# SmartStepp_v2.net
KiCad netlist of a schematic drawn in EAGLE
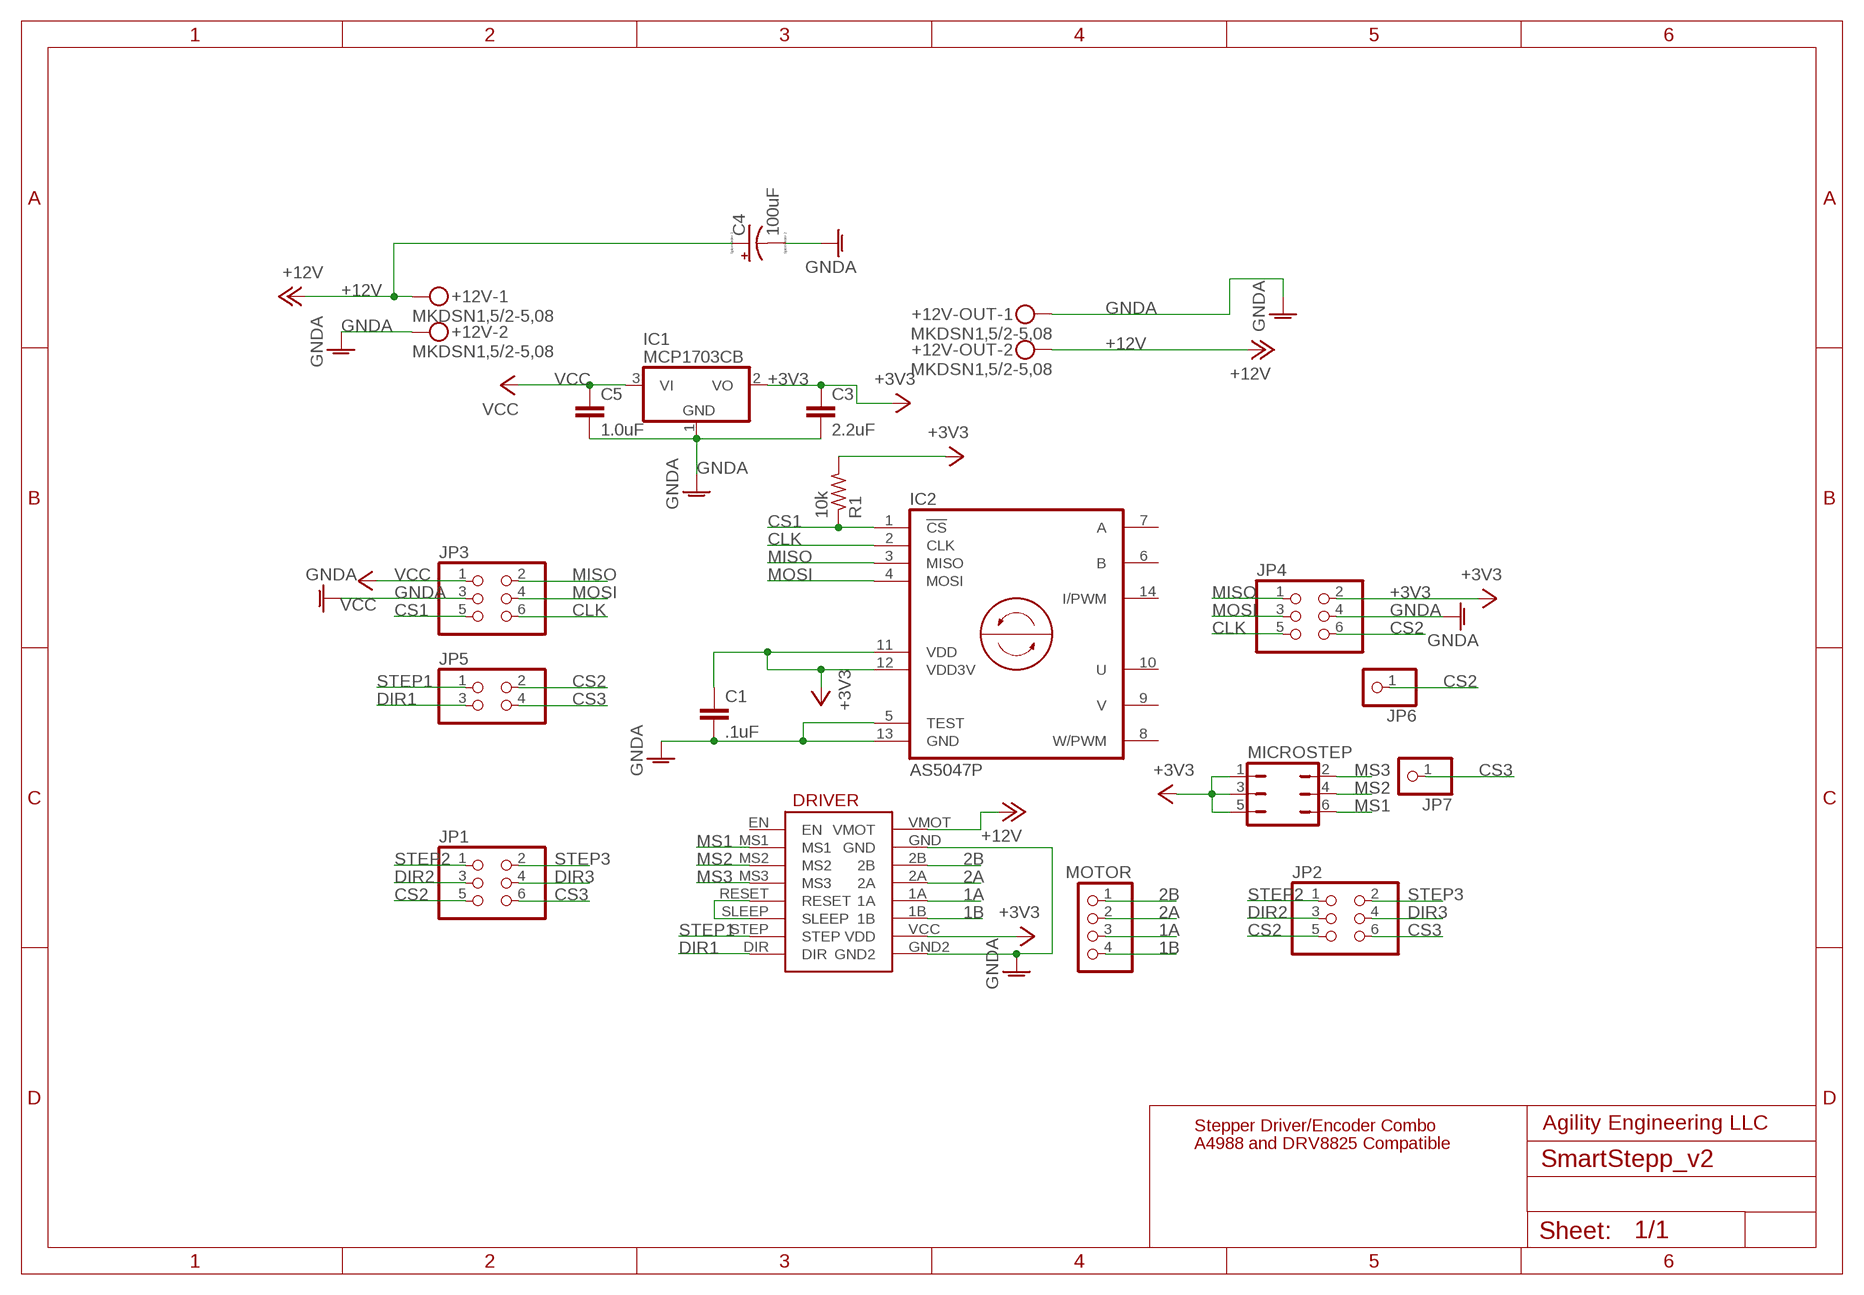
[diagram p0: schematic, sheet 1]

(export (version "E")
  (design (tool "Eeschema 10.0.6"))
  (components
    (comp (ref "+12V")
      (value "MKDSN1,5/2-5,08")
      (footprint "eagle-import:MKDSN1,5_2-5,08")
      (libsource (lib "eagle-import") (part "MKDSN1,5/2-5,08"))
    )
    (comp (ref "+12V-OUT")
      (value "MKDSN1,5/2-5,08")
      (footprint "eagle-import:MKDSN1,5_2-5,08")
      (libsource (lib "eagle-import") (part "MKDSN1,5/2-5,08"))
    )
    (comp (ref "C1")
      (value ".1uF")
      (footprint "eagle-import:C0805")
      (libsource (lib "eagle-import") (part "C-EUC0805"))
    )
    (comp (ref "C3")
      (value "2.2uF")
      (footprint "eagle-import:C0805")
      (libsource (lib "eagle-import") (part "C-EUC0805"))
    )
    (comp (ref "C4")
      (value "100uF")
      (footprint "eagle-import:153CLV-0605")
      (libsource (lib "eagle-import") (part "CPOL-US153CLV-0605"))
    )
    (comp (ref "C5")
      (value "1.0uF")
      (footprint "eagle-import:C0805")
      (libsource (lib "eagle-import") (part "C-EUC0805"))
    )
    (comp (ref "DRIVER")
      (value "A4988")
      (footprint "eagle-import:MOTOR_DRIVER")
      (libsource (lib "eagle-import") (part "A4988"))
    )
    (comp (ref "IC1")
      (value "MCP1703CB")
      (footprint "eagle-import:SOT23")
      (libsource (lib "eagle-import") (part "MCP1703CB"))
    )
    (comp (ref "IC2")
      (value "AS5047P")
      (footprint "eagle-import:TSSOP14")
      (libsource (lib "eagle-import") (part "AS5047P"))
    )
    (comp (ref "JP1")
      (value "PINHD-2X3")
      (footprint "eagle-import:2X03")
      (libsource (lib "eagle-import") (part "PINHD-2X3"))
    )
    (comp (ref "JP2")
      (value "PINHD-2X3")
      (footprint "eagle-import:2X03")
      (libsource (lib "eagle-import") (part "PINHD-2X3"))
    )
    (comp (ref "JP3")
      (value "PINHD-2X3")
      (footprint "eagle-import:2X03")
      (libsource (lib "eagle-import") (part "PINHD-2X3"))
    )
    (comp (ref "JP4")
      (value "PINHD-2X3")
      (footprint "eagle-import:2X03")
      (libsource (lib "eagle-import") (part "PINHD-2X3"))
    )
    (comp (ref "JP5")
      (value "PINHD-2X2")
      (footprint "eagle-import:2X02")
      (libsource (lib "eagle-import") (part "PINHD-2X2"))
    )
    (comp (ref "JP6")
      (value "PINHD-1X1")
      (footprint "eagle-import:1X01")
      (libsource (lib "eagle-import") (part "PINHD-1X1"))
    )
    (comp (ref "JP7")
      (value "PINHD-1X1")
      (footprint "eagle-import:1X01")
      (libsource (lib "eagle-import") (part "PINHD-1X1"))
    )
    (comp (ref "MICROSTEP")
      (value "JP3Q")
      (footprint "eagle-import:JP3Q")
      (libsource (lib "eagle-import") (part "JP3Q"))
    )
    (comp (ref "MOTOR")
      (value "PINHD-1X4")
      (footprint "eagle-import:1X04")
      (libsource (lib "eagle-import") (part "PINHD-1X4"))
    )
    (comp (ref "R1")
      (value "10k")
      (footprint "eagle-import:R0805")
      (libsource (lib "eagle-import") (part "R-US_R0805"))
    )
  )
  (nets
    (net (code "1") (name "+3V3") (class "Default")
      (node (ref "C1") (pin "1") (pinfunction "1_1") (pintype "passive"))
      (node (ref "C3") (pin "1") (pinfunction "1_1") (pintype "passive"))
      (node (ref "DRIVER") (pin "VCC") (pinfunction "VDD_VCC") (pintype "bidirectional"))
      (node (ref "IC1") (pin "2") (pinfunction "VO_2") (pintype "passive"))
      (node (ref "IC2") (pin "11") (pinfunction "VDD_11") (pintype "power_in"))
      (node (ref "IC2") (pin "12") (pinfunction "VDD3V_12") (pintype "power_in"))
      (node (ref "JP4") (pin "2") (pinfunction "2_2") (pintype "passive"))
      (node (ref "MICROSTEP") (pin "1") (pinfunction "1_1") (pintype "passive"))
      (node (ref "MICROSTEP") (pin "3") (pinfunction "3_3") (pintype "passive"))
      (node (ref "MICROSTEP") (pin "5") (pinfunction "5_5") (pintype "passive"))
      (node (ref "R1") (pin "2") (pinfunction "2_2") (pintype "passive"))
    )
    (net (code "2") (name "+12V") (class "Default")
      (node (ref "+12V") (pin "1") (pinfunction "KL_1") (pintype "passive"))
      (node (ref "+12V-OUT") (pin "2") (pinfunction "KL_2") (pintype "passive"))
      (node (ref "C4") (pin "+") (pinfunction "+_+") (pintype "passive"))
      (node (ref "DRIVER") (pin "VMOT") (pinfunction "VMOT_VMOT") (pintype "bidirectional"))
    )
    (net (code "3") (name "/1A") (class "Default")
      (node (ref "DRIVER") (pin "1A") (pinfunction "1A_1A") (pintype "bidirectional"))
      (node (ref "MOTOR") (pin "3") (pinfunction "3_3") (pintype "passive"))
    )
    (net (code "4") (name "/1B") (class "Default")
      (node (ref "DRIVER") (pin "1B") (pinfunction "1B_1B") (pintype "bidirectional"))
      (node (ref "MOTOR") (pin "4") (pinfunction "4_4") (pintype "passive"))
    )
    (net (code "5") (name "/2A") (class "Default")
      (node (ref "DRIVER") (pin "2A") (pinfunction "2A_2A") (pintype "bidirectional"))
      (node (ref "MOTOR") (pin "2") (pinfunction "2_2") (pintype "passive"))
    )
    (net (code "6") (name "/2B") (class "Default")
      (node (ref "DRIVER") (pin "2B") (pinfunction "2B_2B") (pintype "bidirectional"))
      (node (ref "MOTOR") (pin "1") (pinfunction "1_1") (pintype "passive"))
    )
    (net (code "7") (name "/CLK") (class "Default")
      (node (ref "IC2") (pin "2") (pinfunction "CLK_2") (pintype "input"))
      (node (ref "JP3") (pin "6") (pinfunction "6_6") (pintype "passive"))
      (node (ref "JP4") (pin "5") (pinfunction "5_5") (pintype "passive"))
    )
    (net (code "8") (name "/CS1") (class "Default")
      (node (ref "IC2") (pin "1") (pinfunction "~{CS}_1") (pintype "input"))
      (node (ref "JP3") (pin "5") (pinfunction "5_5") (pintype "passive"))
      (node (ref "R1") (pin "1") (pinfunction "1_1") (pintype "passive"))
    )
    (net (code "9") (name "/CS2") (class "Default")
      (node (ref "JP1") (pin "5") (pinfunction "5_5") (pintype "passive"))
      (node (ref "JP2") (pin "5") (pinfunction "5_5") (pintype "passive"))
      (node (ref "JP4") (pin "6") (pinfunction "6_6") (pintype "passive"))
      (node (ref "JP5") (pin "2") (pinfunction "2_2") (pintype "passive"))
      (node (ref "JP6") (pin "1") (pinfunction "1_1") (pintype "passive"))
    )
    (net (code "10") (name "/CS3") (class "Default")
      (node (ref "JP1") (pin "6") (pinfunction "6_6") (pintype "passive"))
      (node (ref "JP2") (pin "6") (pinfunction "6_6") (pintype "passive"))
      (node (ref "JP5") (pin "4") (pinfunction "4_4") (pintype "passive"))
      (node (ref "JP7") (pin "1") (pinfunction "1_1") (pintype "passive"))
    )
    (net (code "11") (name "/DIR1") (class "Default")
      (node (ref "DRIVER") (pin "DIR") (pinfunction "DIR_DIR") (pintype "bidirectional"))
      (node (ref "JP5") (pin "3") (pinfunction "3_3") (pintype "passive"))
    )
    (net (code "12") (name "/DIR2") (class "Default")
      (node (ref "JP1") (pin "3") (pinfunction "3_3") (pintype "passive"))
      (node (ref "JP2") (pin "3") (pinfunction "3_3") (pintype "passive"))
    )
    (net (code "13") (name "/DIR3") (class "Default")
      (node (ref "JP1") (pin "4") (pinfunction "4_4") (pintype "passive"))
      (node (ref "JP2") (pin "4") (pinfunction "4_4") (pintype "passive"))
    )
    (net (code "14") (name "/MISO") (class "Default")
      (node (ref "IC2") (pin "3") (pinfunction "MISO_3") (pintype "output"))
      (node (ref "JP3") (pin "2") (pinfunction "2_2") (pintype "passive"))
      (node (ref "JP4") (pin "1") (pinfunction "1_1") (pintype "passive"))
    )
    (net (code "15") (name "/MOSI") (class "Default")
      (node (ref "IC2") (pin "4") (pinfunction "MOSI_4") (pintype "input"))
      (node (ref "JP3") (pin "4") (pinfunction "4_4") (pintype "passive"))
      (node (ref "JP4") (pin "3") (pinfunction "3_3") (pintype "passive"))
    )
    (net (code "16") (name "/MS1") (class "Default")
      (node (ref "DRIVER") (pin "MS1") (pinfunction "MS1_MS1") (pintype "bidirectional"))
      (node (ref "MICROSTEP") (pin "6") (pinfunction "6_6") (pintype "passive"))
    )
    (net (code "17") (name "/MS2") (class "Default")
      (node (ref "DRIVER") (pin "MS2") (pinfunction "MS2_MS2") (pintype "bidirectional"))
      (node (ref "MICROSTEP") (pin "4") (pinfunction "4_4") (pintype "passive"))
    )
    (net (code "18") (name "/MS3") (class "Default")
      (node (ref "DRIVER") (pin "MS3") (pinfunction "MS3_MS3") (pintype "bidirectional"))
      (node (ref "MICROSTEP") (pin "2") (pinfunction "2_2") (pintype "passive"))
    )
    (net (code "19") (name "/STEP1") (class "Default")
      (node (ref "DRIVER") (pin "STEP") (pinfunction "STEP_STEP") (pintype "bidirectional"))
      (node (ref "JP5") (pin "1") (pinfunction "1_1") (pintype "passive"))
    )
    (net (code "20") (name "/STEP2") (class "Default")
      (node (ref "JP1") (pin "1") (pinfunction "1_1") (pintype "passive"))
      (node (ref "JP2") (pin "1") (pinfunction "1_1") (pintype "passive"))
    )
    (net (code "21") (name "/STEP3") (class "Default")
      (node (ref "JP1") (pin "2") (pinfunction "2_2") (pintype "passive"))
      (node (ref "JP2") (pin "2") (pinfunction "2_2") (pintype "passive"))
    )
    (net (code "22") (name "GNDA") (class "Default")
      (node (ref "+12V") (pin "2") (pinfunction "KL_2") (pintype "passive"))
      (node (ref "+12V-OUT") (pin "1") (pinfunction "KL_1") (pintype "passive"))
      (node (ref "C1") (pin "2") (pinfunction "2_2") (pintype "passive"))
      (node (ref "C3") (pin "2") (pinfunction "2_2") (pintype "passive"))
      (node (ref "C4") (pin "-") (pinfunction "-_-") (pintype "passive"))
      (node (ref "C5") (pin "2") (pinfunction "2_2") (pintype "passive"))
      (node (ref "DRIVER") (pin "GND") (pinfunction "GND_GND") (pintype "bidirectional"))
      (node (ref "DRIVER") (pin "GND2") (pinfunction "GND2_GND2") (pintype "bidirectional"))
      (node (ref "IC1") (pin "1") (pinfunction "GND_1") (pintype "passive"))
      (node (ref "IC2") (pin "13") (pinfunction "GND_13") (pintype "power_in"))
      (node (ref "IC2") (pin "5") (pinfunction "TEST_5") (pintype "input"))
      (node (ref "JP3") (pin "3") (pinfunction "3_3") (pintype "passive"))
      (node (ref "JP4") (pin "4") (pinfunction "4_4") (pintype "passive"))
    )
    (net (code "23") (name "Net-(DRIVER-PadRESET)") (class "Default")
      (node (ref "DRIVER") (pin "RESET") (pinfunction "RESET_RESET") (pintype "bidirectional"))
      (node (ref "DRIVER") (pin "SLEEP") (pinfunction "SLEEP_SLEEP") (pintype "bidirectional"))
    )
    (net (code "24") (name "VCC") (class "Default")
      (node (ref "C5") (pin "1") (pinfunction "1_1") (pintype "passive"))
      (node (ref "IC1") (pin "3") (pinfunction "VI_3") (pintype "input"))
      (node (ref "JP3") (pin "1") (pinfunction "1_1") (pintype "passive"))
    )
    (net (code "25") (name "unconnected-(DRIVER-PadEN)") (class "Default")
      (node (ref "DRIVER") (pin "EN") (pinfunction "EN_EN") (pintype "bidirectional"))
    )
    (net (code "26") (name "unconnected-(IC2-A-Pad7)") (class "Default")
      (node (ref "IC2") (pin "7") (pinfunction "A_7") (pintype "output"))
    )
    (net (code "27") (name "unconnected-(IC2-B-Pad6)") (class "Default")
      (node (ref "IC2") (pin "6") (pinfunction "B_6") (pintype "output"))
    )
    (net (code "28") (name "unconnected-(IC2-I{slash}PWM-Pad14)") (class "Default")
      (node (ref "IC2") (pin "14") (pinfunction "I/PWM_14") (pintype "output"))
    )
    (net (code "29") (name "unconnected-(IC2-U-Pad10)") (class "Default")
      (node (ref "IC2") (pin "10") (pinfunction "U_10") (pintype "output"))
    )
    (net (code "30") (name "unconnected-(IC2-V-Pad9)") (class "Default")
      (node (ref "IC2") (pin "9") (pinfunction "V_9") (pintype "output"))
    )
    (net (code "31") (name "unconnected-(IC2-W{slash}PWM-Pad8)") (class "Default")
      (node (ref "IC2") (pin "8") (pinfunction "W/PWM_8") (pintype "output"))
    )
  )
)
